# 05_-_Power.net
KiCad netlist of a schematic drawn in Altium Designer
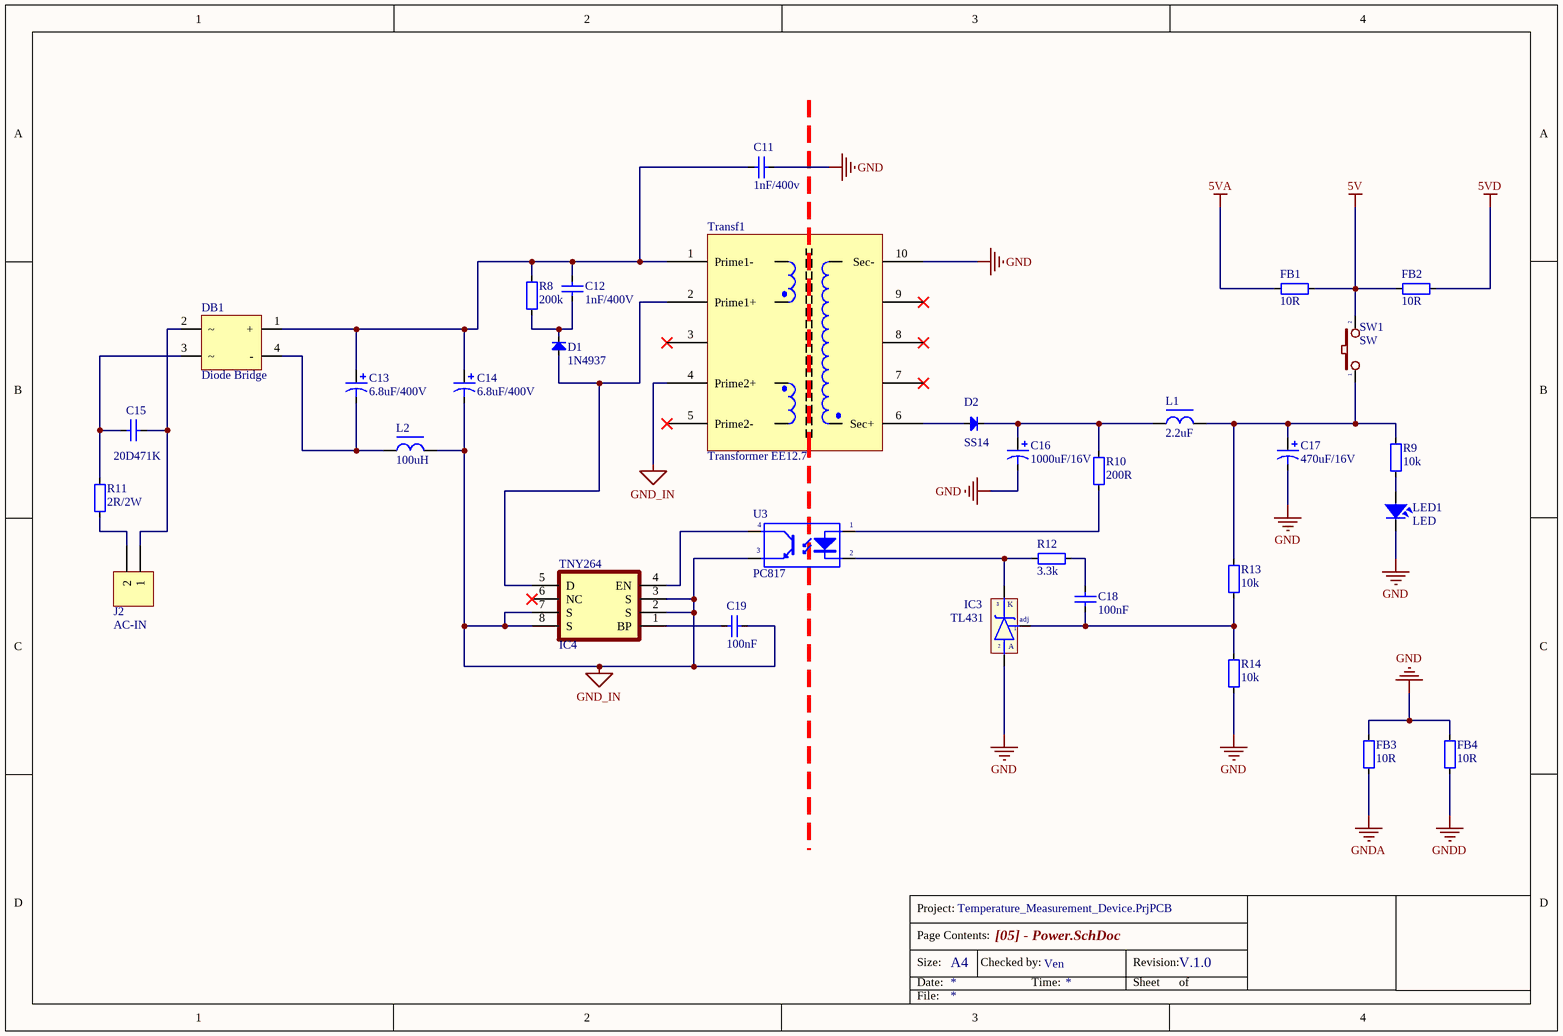
[diagram p0: [05] - Power.SchDoc]

(export (version "E")
  (design (tool "Eeschema 10.0.6"))
  (components
    (comp (ref "C11")
      (value "1nF/400v")
      (footprint "103/2KV")
      (description "CAP CERAMIC")
      (fields (field (name "PUBLISHER") "Altium Limited"))
      (libsource (lib "My Library") (part "Cap2KV"))
    )
    (comp (ref "C12")
      (value "1nF/400V")
      (footprint "103/2KV")
      (description "CAP CERAMIC")
      (fields (field (name "PUBLISHER") "Altium Limited"))
      (libsource (lib "My Library") (part "Cap2KV"))
    )
    (comp (ref "C13")
      (value "6.8uF/400V")
      (footprint "C8mm")
      (description "Polarized Capacitor (Axial)")
      (fields (field (name "PUBLISHER") "Altium Limited"))
      (libsource (lib "My Library") (part "Cap Pol"))
    )
    (comp (ref "C14")
      (value "6.8uF/400V")
      (footprint "C8mm")
      (description "Polarized Capacitor (Axial)")
      (fields (field (name "PUBLISHER") "Altium Limited"))
      (libsource (lib "My Library") (part "Cap Pol"))
    )
    (comp (ref "C15")
      (value "20D471K")
      (footprint "103/2KV")
      (description "Varistor")
      (fields (field (name "PUBLISHER") "Altium Limited"))
      (libsource (lib "My Library") (part "Cap2KV"))
    )
    (comp (ref "C16")
      (value "1000uF/16V")
      (footprint "C8mm")
      (description "Polarized Capacitor (Axial)")
      (fields (field (name "PUBLISHER") "Altium Limited"))
      (libsource (lib "My Library") (part "Cap Pol"))
    )
    (comp (ref "C17")
      (value "470uF/16V")
      (footprint "C8mm")
      (description "Polarized Capacitor (Axial)")
      (fields (field (name "PUBLISHER") "Altium Limited"))
      (libsource (lib "My Library") (part "Cap Pol"))
    )
    (comp (ref "C18")
      (value "100nF")
      (footprint "CAP_0805")
      (description "Capacitor")
      (fields (field (name "PUBLISHER") "Altium Limited"))
      (libsource (lib "My Library") (part "CapSMD"))
    )
    (comp (ref "C19")
      (value "100nF")
      (footprint "CAP_0805")
      (description "Capacitor")
      (fields (field (name "PUBLISHER") "Altium Limited"))
      (libsource (lib "My Library") (part "CapSMD"))
    )
    (comp (ref "D1")
      (value "1N4937")
      (footprint "DIO-1AN")
      (description "Diode Schottky\r\n1N4937")
      (fields (field (name "PUBLISHER") "Altium Limited"))
      (libsource (lib "My Library") (part "Diode SMD"))
    )
    (comp (ref "D2")
      (value "SS14")
      (footprint "DO-214AC(SMA)")
      (description "Diode Schottky\r\n1N5819")
      (fields (field (name "PUBLISHER") "Altium Limited"))
      (libsource (lib "My Library") (part "Diode SMD"))
    )
    (comp (ref "DB1")
      (value "Diode Bridge")
      (footprint "DB207S")
      (libsource (lib "My Library") (part "Diode Bridge Flate"))
    )
    (comp (ref "FB1")
      (value "10R")
      (footprint "RES-SMD-0805")
      (description "Ferrit Bead")
      (fields
        (field (name "MANUFACTURER") "Generic Components")
        (field (name "PUBLISHER") "Altium Hobart Technology Centre")
      )
      (libsource (lib "My Library") (part "Resistor - SMD"))
    )
    (comp (ref "FB2")
      (value "10R")
      (footprint "RES-SMD-0805")
      (description "Ferrit Bead")
      (fields
        (field (name "MANUFACTURER") "Generic Components")
        (field (name "PUBLISHER") "Altium Hobart Technology Centre")
      )
      (libsource (lib "My Library") (part "Resistor - SMD"))
    )
    (comp (ref "FB3")
      (value "10R")
      (footprint "RES-SMD-0805")
      (description "Ferrit Bead")
      (fields
        (field (name "MANUFACTURER") "Generic Components")
        (field (name "PUBLISHER") "Altium Hobart Technology Centre")
      )
      (libsource (lib "My Library") (part "Resistor - SMD"))
    )
    (comp (ref "FB4")
      (value "10R")
      (footprint "RES-SMD-0805")
      (description "Ferrit Bead")
      (fields
        (field (name "MANUFACTURER") "Generic Components")
        (field (name "PUBLISHER") "Altium Hobart Technology Centre")
      )
      (libsource (lib "My Library") (part "Resistor - SMD"))
    )
    (comp (ref "IC3")
      (value "TL431")
      (footprint "qto-92")
      (description "Programmable Shunt Regulator")
      (libsource (lib "My Library") (part "TL431"))
    )
    (comp (ref "IC4")
      (value "TNY264")
      (footprint "DIP8")
      (description "Enhanced, Energy Efficient, Low Power Off-line Switcher")
      (libsource (lib "My Library") (part "TNY264"))
    )
    (comp (ref "J2")
      (value "AC-IN")
      (footprint "KF2-5.08")
      (fields
        (field (name "MANUFACTURER") "Würth Elektronik eiSos GmbH")
        (field (name "PARTNO") "691103110002")
        (field (name "CREATED BY") "Karrer Zheng")
      )
      (libsource (lib "My Library") (part "KF2"))
    )
    (comp (ref "L1")
      (value "2.2uF")
      (footprint "L-SMD-M-7.3x4.5")
      (description "Inductor")
      (libsource (lib "My Library") (part "L-DIP-1"))
    )
    (comp (ref "L2")
      (value "100uH")
      (footprint "L-DIP-M-9.5x6")
      (description "Inductor")
      (libsource (lib "My Library") (part "L-DIP-1"))
    )
    (comp (ref "LED1")
      (value "LED")
      (footprint "LED-0805-Red")
      (description "LED Single colour Green and Red")
      (libsource (lib "My Library") (part "LED"))
    )
    (comp (ref "R8")
      (value "200k")
      (footprint "RES-1/4WD")
      (description "Resistor")
      (fields
        (field (name "MANUFACTURER") "Generic Components")
        (field (name "PUBLISHER") "Altium Hobart Technology Centre")
      )
      (libsource (lib "My Library") (part "Resistor - SMD"))
    )
    (comp (ref "R9")
      (value "10k")
      (footprint "RES-SMD-0805")
      (description "Resistor")
      (fields
        (field (name "MANUFACTURER") "Generic Components")
        (field (name "PUBLISHER") "Altium Hobart Technology Centre")
      )
      (libsource (lib "My Library") (part "Resistor - SMD"))
    )
    (comp (ref "R10")
      (value "200R")
      (footprint "RES-SMD-0805")
      (description "Resistor")
      (fields
        (field (name "MANUFACTURER") "Generic Components")
        (field (name "PUBLISHER") "Altium Hobart Technology Centre")
      )
      (libsource (lib "My Library") (part "Resistor - SMD"))
    )
    (comp (ref "R11")
      (value "2R/2W")
      (footprint "RES-1WD")
      (description "Resistor")
      (fields
        (field (name "MANUFACTURER") "Generic Components")
        (field (name "PUBLISHER") "Altium Hobart Technology Centre")
      )
      (libsource (lib "My Library") (part "Resistor - SMD"))
    )
    (comp (ref "R12")
      (value "3.3k")
      (footprint "RES-SMD-0805")
      (description "Resistor")
      (fields
        (field (name "MANUFACTURER") "Generic Components")
        (field (name "PUBLISHER") "Altium Hobart Technology Centre")
      )
      (libsource (lib "My Library") (part "Resistor - SMD"))
    )
    (comp (ref "R13")
      (value "10k")
      (footprint "RES-SMD-0805")
      (description "Resistor")
      (fields
        (field (name "MANUFACTURER") "Generic Components")
        (field (name "PUBLISHER") "Altium Hobart Technology Centre")
      )
      (libsource (lib "My Library") (part "Resistor - SMD"))
    )
    (comp (ref "R14")
      (value "10k")
      (footprint "RES-SMD-0805")
      (description "Resistor")
      (fields
        (field (name "MANUFACTURER") "Generic Components")
        (field (name "PUBLISHER") "Altium Hobart Technology Centre")
      )
      (libsource (lib "My Library") (part "Resistor - SMD"))
    )
    (comp (ref "SW1")
      (value "SW")
      (footprint "SW2")
      (description "Switch button 2 pin")
      (libsource (lib "My Library") (part "SW2"))
    )
    (comp (ref "Transf1")
      (value "Transformer EE12.7")
      (footprint "Transformer EE12.7")
      (libsource (lib "My Library") (part "Tranformer EE16"))
    )
    (comp (ref "U3")
      (value "PC817")
      (footprint "DIP4/W0.3")
      (description "Single Opto")
      (libsource (lib "My Library") (part "PC817"))
    )
  )
  (nets
    (net (code "1") (name "5V") (class "Default")
      (node (ref "FB1") (pin "2") (pinfunction "2_2") (pintype "passive"))
      (node (ref "FB2") (pin "1") (pinfunction "1_1") (pintype "passive"))
      (node (ref "SW1") (pin "2") (pinfunction "2_2") (pintype "passive"))
    )
    (net (code "2") (name "5VA") (class "Default")
      (node (ref "FB1") (pin "1") (pinfunction "1_1") (pintype "passive"))
    )
    (net (code "3") (name "5VD") (class "Default")
      (node (ref "FB2") (pin "2") (pinfunction "2_2") (pintype "passive"))
    )
    (net (code "4") (name "GND") (class "Default")
      (node (ref "C11") (pin "1") (pinfunction "1_1") (pintype "passive"))
      (node (ref "C16") (pin "2") (pinfunction "2_2") (pintype "passive"))
      (node (ref "C17") (pin "2") (pinfunction "2_2") (pintype "passive"))
      (node (ref "FB3") (pin "2") (pinfunction "2_2") (pintype "passive"))
      (node (ref "FB4") (pin "2") (pinfunction "2_2") (pintype "passive"))
      (node (ref "IC3") (pin "2") (pinfunction "A_2") (pintype "passive"))
      (node (ref "LED1") (pin "2") (pinfunction "2_2") (pintype "passive"))
      (node (ref "R14") (pin "2") (pinfunction "2_2") (pintype "passive"))
      (node (ref "Transf1") (pin "10") (pinfunction "Sec-_10") (pintype "passive"))
    )
    (net (code "5") (name "GNDA") (class "Default")
      (node (ref "FB3") (pin "1") (pinfunction "1_1") (pintype "passive"))
    )
    (net (code "6") (name "GNDD") (class "Default")
      (node (ref "FB4") (pin "1") (pinfunction "1_1") (pintype "passive"))
    )
    (net (code "7") (name "GND_IN") (class "Default")
      (node (ref "C14") (pin "2") (pinfunction "2_2") (pintype "passive"))
      (node (ref "C19") (pin "1") (pinfunction "1_1") (pintype "passive"))
      (node (ref "IC4") (pin "2") (pinfunction "S_2") (pintype "power_in"))
      (node (ref "IC4") (pin "3") (pinfunction "S_3") (pintype "power_in"))
      (node (ref "IC4") (pin "7") (pinfunction "S_7") (pintype "power_in"))
      (node (ref "IC4") (pin "8") (pinfunction "S_8") (pintype "power_in"))
      (node (ref "L2") (pin "2") (pinfunction "2_2") (pintype "passive"))
      (node (ref "Transf1") (pin "4") (pinfunction "Prime2+_4") (pintype "passive"))
      (node (ref "U3") (pin "3") (pinfunction "E_3") (pintype "passive"))
    )
    (net (code "8") (name "Net-(C15-Pad1)") (class "Default")
      (node (ref "C15") (pin "1") (pinfunction "1_1") (pintype "passive"))
      (node (ref "DB1") (pin "2") (pinfunction "~_2") (pintype "passive"))
      (node (ref "J2") (pin "1") (pinfunction "1_1") (pintype "passive"))
    )
    (net (code "9") (name "Net-(C15-Pad2)") (class "Default")
      (node (ref "C15") (pin "2") (pinfunction "2_2") (pintype "passive"))
      (node (ref "DB1") (pin "3") (pinfunction "~_3") (pintype "passive"))
      (node (ref "R11") (pin "1") (pinfunction "1_1") (pintype "passive"))
    )
    (net (code "10") (name "Net-(C17-Pad1)") (class "Default")
      (node (ref "C17") (pin "1") (pinfunction "1_1") (pintype "passive"))
      (node (ref "L1") (pin "2") (pinfunction "2_2") (pintype "passive"))
      (node (ref "R13") (pin "1") (pinfunction "1_1") (pintype "passive"))
      (node (ref "R9") (pin "1") (pinfunction "1_1") (pintype "passive"))
      (node (ref "SW1") (pin "1") (pinfunction "1_1") (pintype "passive"))
    )
    (net (code "11") (name "Net-(C18-Pad2)") (class "Default")
      (node (ref "C18") (pin "2") (pinfunction "2_2") (pintype "passive"))
      (node (ref "R12") (pin "2") (pinfunction "2_2") (pintype "passive"))
    )
    (net (code "12") (name "Net-(D1-A)") (class "Default")
      (node (ref "D1") (pin "1") (pinfunction "A_1") (pintype "passive"))
      (node (ref "IC4") (pin "5") (pinfunction "D_5") (pintype "power_in"))
      (node (ref "Transf1") (pin "2") (pinfunction "Prime1+_2") (pintype "passive"))
    )
    (net (code "13") (name "Net-(D1-K)") (class "Default")
      (node (ref "C12") (pin "2") (pinfunction "2_2") (pintype "passive"))
      (node (ref "D1") (pin "2") (pinfunction "K_2") (pintype "passive"))
      (node (ref "R8") (pin "1") (pinfunction "1_1") (pintype "passive"))
    )
    (net (code "14") (name "Net-(D2-A)") (class "Default")
      (node (ref "D2") (pin "1") (pinfunction "A_1") (pintype "passive"))
      (node (ref "Transf1") (pin "6") (pinfunction "Sec+_6") (pintype "passive"))
    )
    (net (code "15") (name "Net-(D2-K)") (class "Default")
      (node (ref "C16") (pin "1") (pinfunction "1_1") (pintype "passive"))
      (node (ref "D2") (pin "2") (pinfunction "K_2") (pintype "passive"))
      (node (ref "L1") (pin "1") (pinfunction "1_1") (pintype "passive"))
      (node (ref "R10") (pin "1") (pinfunction "1_1") (pintype "passive"))
    )
    (net (code "16") (name "Net-(DB1-+)") (class "Default")
      (node (ref "C11") (pin "2") (pinfunction "2_2") (pintype "passive"))
      (node (ref "C12") (pin "1") (pinfunction "1_1") (pintype "passive"))
      (node (ref "C13") (pin "1") (pinfunction "1_1") (pintype "passive"))
      (node (ref "C14") (pin "1") (pinfunction "1_1") (pintype "passive"))
      (node (ref "DB1") (pin "1") (pinfunction "+_1") (pintype "passive"))
      (node (ref "R8") (pin "2") (pinfunction "2_2") (pintype "passive"))
      (node (ref "Transf1") (pin "1") (pinfunction "Prime1-_1") (pintype "passive"))
    )
    (net (code "17") (name "Net-(DB1--)") (class "Default")
      (node (ref "C13") (pin "2") (pinfunction "2_2") (pintype "passive"))
      (node (ref "DB1") (pin "4") (pinfunction "-_4") (pintype "passive"))
      (node (ref "L2") (pin "1") (pinfunction "1_1") (pintype "passive"))
    )
    (net (code "18") (name "Net-(IC3-K)") (class "Default")
      (node (ref "IC3") (pin "3") (pinfunction "K_3") (pintype "passive"))
      (node (ref "R12") (pin "1") (pinfunction "1_1") (pintype "passive"))
      (node (ref "U3") (pin "2") (pinfunction "K_2") (pintype "passive"))
    )
    (net (code "19") (name "Net-(IC3-adj)") (class "Default")
      (node (ref "C18") (pin "1") (pinfunction "1_1") (pintype "passive"))
      (node (ref "IC3") (pin "1") (pinfunction "adj_1") (pintype "passive"))
      (node (ref "R13") (pin "2") (pinfunction "2_2") (pintype "passive"))
      (node (ref "R14") (pin "1") (pinfunction "1_1") (pintype "passive"))
    )
    (net (code "20") (name "Net-(IC4-BP)") (class "Default")
      (node (ref "C19") (pin "2") (pinfunction "2_2") (pintype "passive"))
      (node (ref "IC4") (pin "1") (pinfunction "BP_1") (pintype "power_in"))
    )
    (net (code "21") (name "Net-(IC4-EN)") (class "Default")
      (node (ref "IC4") (pin "4") (pinfunction "EN_4") (pintype "power_in"))
      (node (ref "U3") (pin "4") (pinfunction "C_4") (pintype "passive"))
    )
    (net (code "22") (name "Net-(J2-Pad2)") (class "Default")
      (node (ref "J2") (pin "2") (pinfunction "2_2") (pintype "passive"))
      (node (ref "R11") (pin "2") (pinfunction "2_2") (pintype "passive"))
    )
    (net (code "23") (name "Net-(LED1-Pad1)") (class "Default")
      (node (ref "LED1") (pin "1") (pinfunction "1_1") (pintype "passive"))
      (node (ref "R9") (pin "2") (pinfunction "2_2") (pintype "passive"))
    )
    (net (code "24") (name "Net-(U3-A)") (class "Default")
      (node (ref "R10") (pin "2") (pinfunction "2_2") (pintype "passive"))
      (node (ref "U3") (pin "1") (pinfunction "A_1") (pintype "passive"))
    )
    (net (code "25") (name "unconnected-(IC4-NC-Pad6)") (class "Default")
      (node (ref "IC4") (pin "6") (pinfunction "NC_6") (pintype "power_in+no_connect"))
    )
    (net (code "26") (name "unconnected-(Transf1-Pad3)") (class "Default")
      (node (ref "Transf1") (pin "3") (pintype "passive+no_connect"))
    )
    (net (code "27") (name "unconnected-(Transf1-Pad7)") (class "Default")
      (node (ref "Transf1") (pin "7") (pintype "passive+no_connect"))
    )
    (net (code "28") (name "unconnected-(Transf1-Pad8)") (class "Default")
      (node (ref "Transf1") (pin "8") (pintype "passive+no_connect"))
    )
    (net (code "29") (name "unconnected-(Transf1-Pad9)") (class "Default")
      (node (ref "Transf1") (pin "9") (pintype "passive+no_connect"))
    )
    (net (code "30") (name "unconnected-(Transf1-Prime2--Pad5)") (class "Default")
      (node (ref "Transf1") (pin "5") (pinfunction "Prime2-_5") (pintype "passive+no_connect"))
    )
  )
)
